# ESC_4in1.net
KiCad netlist of a schematic drawn in Altium Designer
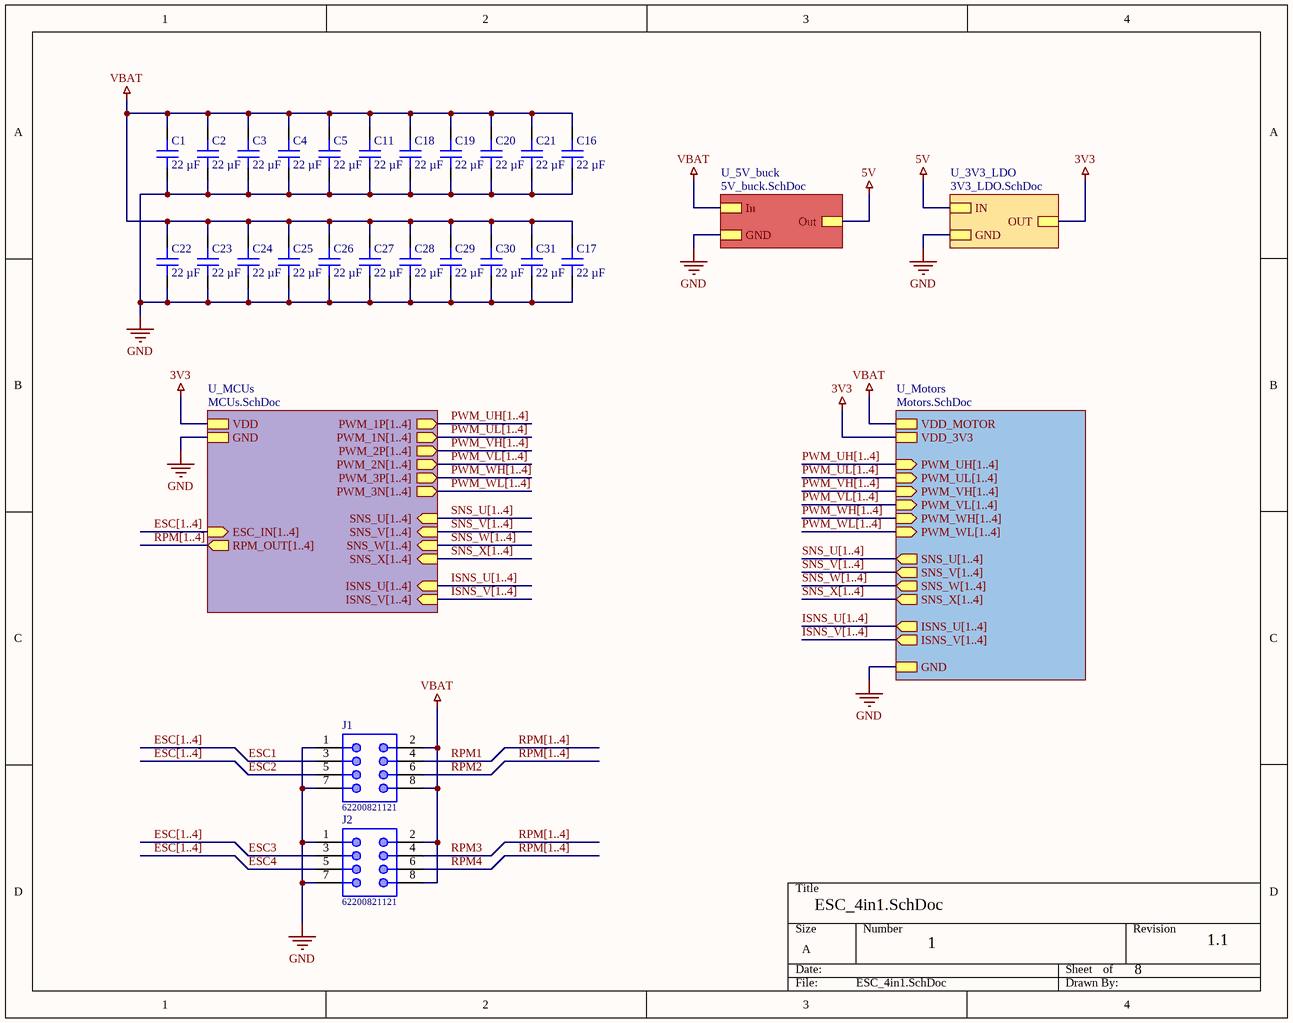
[diagram p0: ESC_4in1.SchDoc]

(export (version "E")
  (design (tool "Eeschema 10.0.6"))
  (components
    (comp (ref "C1")
      (value "22 µF")
      (footprint "CAP 0805_2012")
      (description "CAP CER 22UF 25V X5R 0805")
      (fields (field (name "PART NUMBER") "CC0805MKX5R8BB226") (field (name "MANUFACTURER") "Yageo"))
      (libsource (lib "Celestial Altium Library - altium_library") (part "Capacitor"))
    )
    (comp (ref "C2")
      (value "22 µF")
      (footprint "CAP 0805_2012")
      (description "CAP CER 22UF 25V X5R 0805")
      (fields (field (name "PART NUMBER") "CC0805MKX5R8BB226") (field (name "MANUFACTURER") "Yageo"))
      (libsource (lib "Celestial Altium Library - altium_library") (part "Capacitor"))
    )
    (comp (ref "C3")
      (value "22 µF")
      (footprint "CAP 0805_2012")
      (description "CAP CER 22UF 25V X5R 0805")
      (fields (field (name "PART NUMBER") "CC0805MKX5R8BB226") (field (name "MANUFACTURER") "Yageo"))
      (libsource (lib "Celestial Altium Library - altium_library") (part "Capacitor"))
    )
    (comp (ref "C4")
      (value "22 µF")
      (footprint "CAP 0805_2012")
      (description "CAP CER 22UF 25V X5R 0805")
      (fields (field (name "PART NUMBER") "CC0805MKX5R8BB226") (field (name "MANUFACTURER") "Yageo"))
      (libsource (lib "Celestial Altium Library - altium_library") (part "Capacitor"))
    )
    (comp (ref "C5")
      (value "22 µF")
      (footprint "CAP 0805_2012")
      (description "CAP CER 22UF 25V X5R 0805")
      (fields (field (name "PART NUMBER") "CC0805MKX5R8BB226") (field (name "MANUFACTURER") "Yageo"))
      (libsource (lib "Celestial Altium Library - altium_library") (part "Capacitor"))
    )
    (comp (ref "C11")
      (value "22 µF")
      (footprint "CAP 0805_2012")
      (description "CAP CER 22UF 25V X5R 0805")
      (fields (field (name "PART NUMBER") "CC0805MKX5R8BB226") (field (name "MANUFACTURER") "Yageo"))
      (libsource (lib "Celestial Altium Library - altium_library") (part "Capacitor"))
    )
    (comp (ref "C16")
      (value "22 µF")
      (footprint "CAP 0805_2012")
      (description "CAP CER 22UF 25V X5R 0805")
      (fields (field (name "PART NUMBER") "CC0805MKX5R8BB226") (field (name "MANUFACTURER") "Yageo"))
      (libsource (lib "Celestial Altium Library - altium_library") (part "Capacitor"))
    )
    (comp (ref "C17")
      (value "22 µF")
      (footprint "CAP 0805_2012")
      (description "CAP CER 22UF 25V X5R 0805")
      (fields (field (name "PART NUMBER") "CC0805MKX5R8BB226") (field (name "MANUFACTURER") "Yageo"))
      (libsource (lib "Celestial Altium Library - altium_library") (part "Capacitor"))
    )
    (comp (ref "C18")
      (value "22 µF")
      (footprint "CAP 0805_2012")
      (description "CAP CER 22UF 25V X5R 0805")
      (fields (field (name "PART NUMBER") "CC0805MKX5R8BB226") (field (name "MANUFACTURER") "Yageo"))
      (libsource (lib "Celestial Altium Library - altium_library") (part "Capacitor"))
    )
    (comp (ref "C19")
      (value "22 µF")
      (footprint "CAP 0805_2012")
      (description "CAP CER 22UF 25V X5R 0805")
      (fields (field (name "PART NUMBER") "CC0805MKX5R8BB226") (field (name "MANUFACTURER") "Yageo"))
      (libsource (lib "Celestial Altium Library - altium_library") (part "Capacitor"))
    )
    (comp (ref "C20")
      (value "22 µF")
      (footprint "CAP 0805_2012")
      (description "CAP CER 22UF 25V X5R 0805")
      (fields (field (name "PART NUMBER") "CC0805MKX5R8BB226") (field (name "MANUFACTURER") "Yageo"))
      (libsource (lib "Celestial Altium Library - altium_library") (part "Capacitor"))
    )
    (comp (ref "C21")
      (value "22 µF")
      (footprint "CAP 0805_2012")
      (description "CAP CER 22UF 25V X5R 0805")
      (fields (field (name "PART NUMBER") "CC0805MKX5R8BB226") (field (name "MANUFACTURER") "Yageo"))
      (libsource (lib "Celestial Altium Library - altium_library") (part "Capacitor"))
    )
    (comp (ref "C22")
      (value "22 µF")
      (footprint "CAP 0805_2012")
      (description "CAP CER 22UF 25V X5R 0805")
      (fields (field (name "PART NUMBER") "CC0805MKX5R8BB226") (field (name "MANUFACTURER") "Yageo"))
      (libsource (lib "Celestial Altium Library - altium_library") (part "Capacitor"))
    )
    (comp (ref "C23")
      (value "22 µF")
      (footprint "CAP 0805_2012")
      (description "CAP CER 22UF 25V X5R 0805")
      (fields (field (name "PART NUMBER") "CC0805MKX5R8BB226") (field (name "MANUFACTURER") "Yageo"))
      (libsource (lib "Celestial Altium Library - altium_library") (part "Capacitor"))
    )
    (comp (ref "C24")
      (value "22 µF")
      (footprint "CAP 0805_2012")
      (description "CAP CER 22UF 25V X5R 0805")
      (fields (field (name "PART NUMBER") "CC0805MKX5R8BB226") (field (name "MANUFACTURER") "Yageo"))
      (libsource (lib "Celestial Altium Library - altium_library") (part "Capacitor"))
    )
    (comp (ref "C25")
      (value "22 µF")
      (footprint "CAP 0805_2012")
      (description "CAP CER 22UF 25V X5R 0805")
      (fields (field (name "PART NUMBER") "CC0805MKX5R8BB226") (field (name "MANUFACTURER") "Yageo"))
      (libsource (lib "Celestial Altium Library - altium_library") (part "Capacitor"))
    )
    (comp (ref "C26")
      (value "22 µF")
      (footprint "CAP 0805_2012")
      (description "CAP CER 22UF 25V X5R 0805")
      (fields (field (name "PART NUMBER") "CC0805MKX5R8BB226") (field (name "MANUFACTURER") "Yageo"))
      (libsource (lib "Celestial Altium Library - altium_library") (part "Capacitor"))
    )
    (comp (ref "C27")
      (value "22 µF")
      (footprint "CAP 0805_2012")
      (description "CAP CER 22UF 25V X5R 0805")
      (fields (field (name "PART NUMBER") "CC0805MKX5R8BB226") (field (name "MANUFACTURER") "Yageo"))
      (libsource (lib "Celestial Altium Library - altium_library") (part "Capacitor"))
    )
    (comp (ref "C28")
      (value "22 µF")
      (footprint "CAP 0805_2012")
      (description "CAP CER 22UF 25V X5R 0805")
      (fields (field (name "PART NUMBER") "CC0805MKX5R8BB226") (field (name "MANUFACTURER") "Yageo"))
      (libsource (lib "Celestial Altium Library - altium_library") (part "Capacitor"))
    )
    (comp (ref "C29")
      (value "22 µF")
      (footprint "CAP 0805_2012")
      (description "CAP CER 22UF 25V X5R 0805")
      (fields (field (name "PART NUMBER") "CC0805MKX5R8BB226") (field (name "MANUFACTURER") "Yageo"))
      (libsource (lib "Celestial Altium Library - altium_library") (part "Capacitor"))
    )
    (comp (ref "C30")
      (value "22 µF")
      (footprint "CAP 0805_2012")
      (description "CAP CER 22UF 25V X5R 0805")
      (fields (field (name "PART NUMBER") "CC0805MKX5R8BB226") (field (name "MANUFACTURER") "Yageo"))
      (libsource (lib "Celestial Altium Library - altium_library") (part "Capacitor"))
    )
    (comp (ref "C31")
      (value "22 µF")
      (footprint "CAP 0805_2012")
      (description "CAP CER 22UF 25V X5R 0805")
      (fields (field (name "PART NUMBER") "CC0805MKX5R8BB226") (field (name "MANUFACTURER") "Yageo"))
      (libsource (lib "Celestial Altium Library - altium_library") (part "Capacitor"))
    )
    (comp (ref "J1")
      (value "62200821121")
      (footprint "62200821121")
      (description "WR-PHD Pin Header, THT, pitch 1.27mm, Dual Row, Vertical, 8p")
      (fields (field (name "MANUFACTURER") "Wurth Elektronik"))
      (libsource (lib "Altium_WR-PHD") (part "62200821121"))
    )
    (comp (ref "J2")
      (value "62200821121")
      (footprint "62200821121")
      (description "WR-PHD Pin Header, THT, pitch 1.27mm, Dual Row, Vertical, 8p")
      (fields (field (name "MANUFACTURER") "Wurth Elektronik"))
      (libsource (lib "Altium_WR-PHD") (part "62200821121"))
    )
  )
  (nets
    (net (code "49") (name "/ESC1") (class "Default")
      (node (ref "J1") (pin "3") (pinfunction "3_3") (pintype "passive"))
    )
    (net (code "50") (name "/ESC2") (class "Default")
      (node (ref "J1") (pin "5") (pinfunction "5_5") (pintype "passive"))
    )
    (net (code "51") (name "/ESC3") (class "Default")
      (node (ref "J2") (pin "3") (pinfunction "3_3") (pintype "passive"))
    )
    (net (code "52") (name "/ESC4") (class "Default")
      (node (ref "J2") (pin "5") (pinfunction "5_5") (pintype "passive"))
    )
    (net (code "62") (name "/RPM1") (class "Default")
      (node (ref "J1") (pin "4") (pinfunction "4_4") (pintype "passive"))
    )
    (net (code "63") (name "/RPM2") (class "Default")
      (node (ref "J1") (pin "6") (pinfunction "6_6") (pintype "passive"))
    )
    (net (code "64") (name "/RPM3") (class "Default")
      (node (ref "J2") (pin "4") (pinfunction "4_4") (pintype "passive"))
    )
    (net (code "65") (name "/RPM4") (class "Default")
      (node (ref "J2") (pin "6") (pinfunction "6_6") (pintype "passive"))
    )
    (net (code "73") (name "GND") (class "Default")
      (node (ref "C1") (pin "1") (pinfunction "1_1") (pintype "passive"))
      (node (ref "C11") (pin "1") (pinfunction "1_1") (pintype "passive"))
      (node (ref "C16") (pin "1") (pinfunction "1_1") (pintype "passive"))
      (node (ref "C17") (pin "1") (pinfunction "1_1") (pintype "passive"))
      (node (ref "C18") (pin "1") (pinfunction "1_1") (pintype "passive"))
      (node (ref "C19") (pin "1") (pinfunction "1_1") (pintype "passive"))
      (node (ref "C2") (pin "1") (pinfunction "1_1") (pintype "passive"))
      (node (ref "C20") (pin "1") (pinfunction "1_1") (pintype "passive"))
      (node (ref "C21") (pin "1") (pinfunction "1_1") (pintype "passive"))
      (node (ref "C22") (pin "1") (pinfunction "1_1") (pintype "passive"))
      (node (ref "C23") (pin "1") (pinfunction "1_1") (pintype "passive"))
      (node (ref "C24") (pin "1") (pinfunction "1_1") (pintype "passive"))
      (node (ref "C25") (pin "1") (pinfunction "1_1") (pintype "passive"))
      (node (ref "C26") (pin "1") (pinfunction "1_1") (pintype "passive"))
      (node (ref "C27") (pin "1") (pinfunction "1_1") (pintype "passive"))
      (node (ref "C28") (pin "1") (pinfunction "1_1") (pintype "passive"))
      (node (ref "C29") (pin "1") (pinfunction "1_1") (pintype "passive"))
      (node (ref "C3") (pin "1") (pinfunction "1_1") (pintype "passive"))
      (node (ref "C30") (pin "1") (pinfunction "1_1") (pintype "passive"))
      (node (ref "C31") (pin "1") (pinfunction "1_1") (pintype "passive"))
      (node (ref "C4") (pin "1") (pinfunction "1_1") (pintype "passive"))
      (node (ref "C5") (pin "1") (pinfunction "1_1") (pintype "passive"))
      (node (ref "J1") (pin "1") (pinfunction "1_1") (pintype "passive"))
      (node (ref "J1") (pin "7") (pinfunction "7_7") (pintype "passive"))
      (node (ref "J2") (pin "1") (pinfunction "1_1") (pintype "passive"))
      (node (ref "J2") (pin "7") (pinfunction "7_7") (pintype "passive"))
    )
    (net (code "74") (name "VBAT") (class "Default")
      (node (ref "C1") (pin "2") (pinfunction "2_2") (pintype "passive"))
      (node (ref "C11") (pin "2") (pinfunction "2_2") (pintype "passive"))
      (node (ref "C16") (pin "2") (pinfunction "2_2") (pintype "passive"))
      (node (ref "C17") (pin "2") (pinfunction "2_2") (pintype "passive"))
      (node (ref "C18") (pin "2") (pinfunction "2_2") (pintype "passive"))
      (node (ref "C19") (pin "2") (pinfunction "2_2") (pintype "passive"))
      (node (ref "C2") (pin "2") (pinfunction "2_2") (pintype "passive"))
      (node (ref "C20") (pin "2") (pinfunction "2_2") (pintype "passive"))
      (node (ref "C21") (pin "2") (pinfunction "2_2") (pintype "passive"))
      (node (ref "C22") (pin "2") (pinfunction "2_2") (pintype "passive"))
      (node (ref "C23") (pin "2") (pinfunction "2_2") (pintype "passive"))
      (node (ref "C24") (pin "2") (pinfunction "2_2") (pintype "passive"))
      (node (ref "C25") (pin "2") (pinfunction "2_2") (pintype "passive"))
      (node (ref "C26") (pin "2") (pinfunction "2_2") (pintype "passive"))
      (node (ref "C27") (pin "2") (pinfunction "2_2") (pintype "passive"))
      (node (ref "C28") (pin "2") (pinfunction "2_2") (pintype "passive"))
      (node (ref "C29") (pin "2") (pinfunction "2_2") (pintype "passive"))
      (node (ref "C3") (pin "2") (pinfunction "2_2") (pintype "passive"))
      (node (ref "C30") (pin "2") (pinfunction "2_2") (pintype "passive"))
      (node (ref "C31") (pin "2") (pinfunction "2_2") (pintype "passive"))
      (node (ref "C4") (pin "2") (pinfunction "2_2") (pintype "passive"))
      (node (ref "C5") (pin "2") (pinfunction "2_2") (pintype "passive"))
      (node (ref "J1") (pin "2") (pinfunction "2_2") (pintype "passive"))
      (node (ref "J1") (pin "8") (pinfunction "8_8") (pintype "passive"))
      (node (ref "J2") (pin "2") (pinfunction "2_2") (pintype "passive"))
      (node (ref "J2") (pin "8") (pinfunction "8_8") (pintype "passive"))
    )
  )
)
